# Buttoninterface.net
KiCad netlist of a schematic drawn in Altium Designer
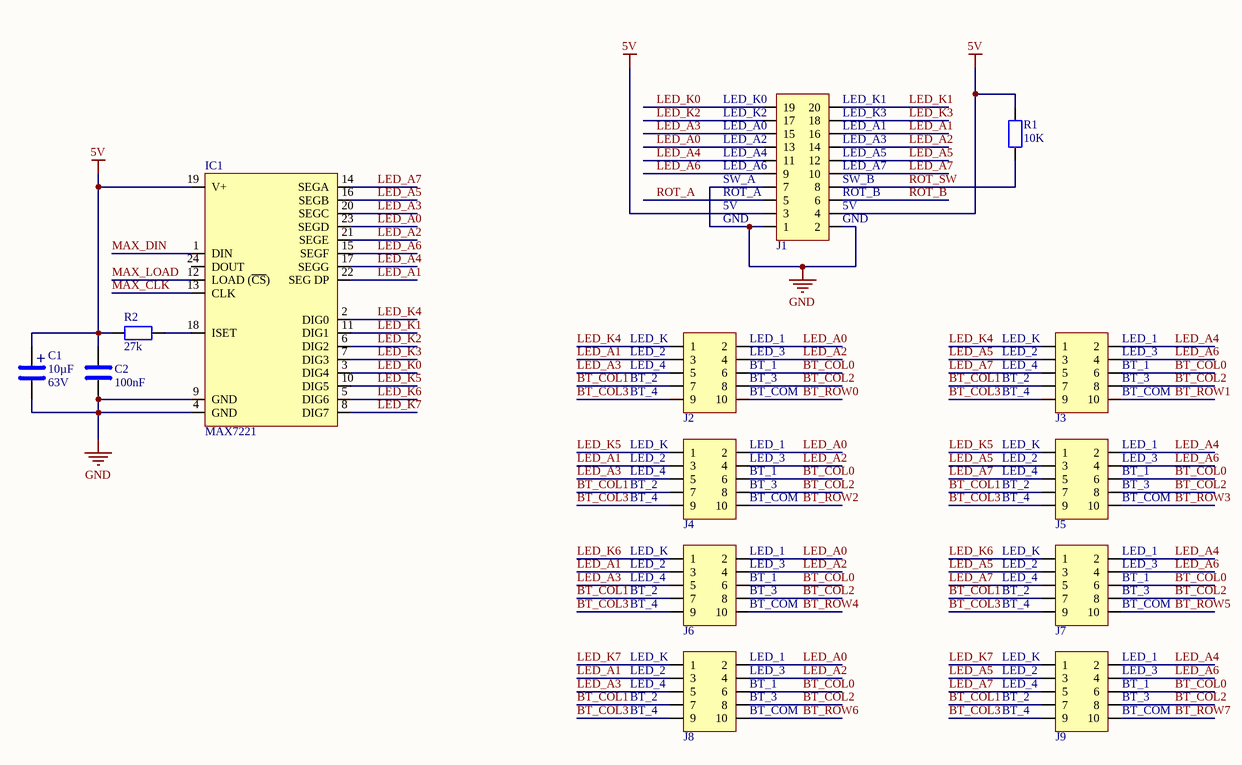
[diagram p0: Buttoninterface.SchDoc]

(export (version "E")
  (design (tool "Eeschema 10.0.6"))
  (components
    (comp (ref "C1")
      (value "10µF")
      (footprint "RM2D5H11")
      (fields (field (name "VOLTAGE") "63V") (field (name "Comment") "Elko_10uF_63V"))
      (libsource (lib "elkos") (part "Elko_10uF_63V"))
    )
    (comp (ref "C2")
      (value "100nF")
      (footprint "0805")
      (description "100nF 50V MLCC 0805")
      (fields (field (name "VOLTAGE") "50V"))
      (libsource (lib "capacitors") (part "100nF 50V MLCC 0805"))
    )
    (comp (ref "IC1")
      (value "MAX7221")
      (footprint "DIL28")
      (description "8x8 Matrix LED driver")
      (libsource (lib "misc") (part "MAX7221CNG"))
    )
    (comp (ref "J1")
      (value "Wannenstecker 20pol 2,54mm")
      (footprint "WSL20G")
      (libsource (lib "wannenstecker") (part "Wannenstecker 20pol 2,54mm"))
    )
    (comp (ref "J2")
      (value "Wannenstecker 10pol 2,54mm")
      (footprint "WSL10G")
      (libsource (lib "wannenstecker") (part "Wannenstecker 10pol 2,54mm"))
    )
    (comp (ref "J3")
      (value "Wannenstecker 10pol 2,54mm")
      (footprint "WSL10G")
      (libsource (lib "wannenstecker") (part "Wannenstecker 10pol 2,54mm"))
    )
    (comp (ref "J4")
      (value "Wannenstecker 10pol 2,54mm")
      (footprint "WSL10G")
      (libsource (lib "wannenstecker") (part "Wannenstecker 10pol 2,54mm"))
    )
    (comp (ref "J5")
      (value "Wannenstecker 10pol 2,54mm")
      (footprint "WSL10G")
      (libsource (lib "wannenstecker") (part "Wannenstecker 10pol 2,54mm"))
    )
    (comp (ref "J6")
      (value "Wannenstecker 10pol 2,54mm")
      (footprint "WSL10G")
      (libsource (lib "wannenstecker") (part "Wannenstecker 10pol 2,54mm"))
    )
    (comp (ref "J7")
      (value "Wannenstecker 10pol 2,54mm")
      (footprint "WSL10G")
      (libsource (lib "wannenstecker") (part "Wannenstecker 10pol 2,54mm"))
    )
    (comp (ref "J8")
      (value "Wannenstecker 10pol 2,54mm")
      (footprint "WSL10G")
      (libsource (lib "wannenstecker") (part "Wannenstecker 10pol 2,54mm"))
    )
    (comp (ref "J9")
      (value "Wannenstecker 10pol 2,54mm")
      (footprint "WSL10G")
      (libsource (lib "wannenstecker") (part "Wannenstecker 10pol 2,54mm"))
    )
    (comp (ref "R1")
      (value "10K")
      (footprint "res0805")
      (description "10K 125mW 0805")
      (fields (field (name "TOLERANCE") "1%"))
      (libsource (lib "resistors") (part "10K 125mW 0805"))
    )
    (comp (ref "R2")
      (value "27k")
      (footprint "res0805")
      (description "27k 125mW 0805")
      (fields (field (name "TOLERANCE") "1%"))
      (libsource (lib "resistors") (part "27k 125mW 0805"))
    )
  )
  (nets
    (net (code "1") (name "/BT_COL0") (class "Default")
      (node (ref "J2") (pin "6") (pinfunction "6_6") (pintype "passive"))
      (node (ref "J3") (pin "6") (pinfunction "6_6") (pintype "passive"))
      (node (ref "J4") (pin "6") (pinfunction "6_6") (pintype "passive"))
      (node (ref "J5") (pin "6") (pinfunction "6_6") (pintype "passive"))
      (node (ref "J6") (pin "6") (pinfunction "6_6") (pintype "passive"))
      (node (ref "J7") (pin "6") (pinfunction "6_6") (pintype "passive"))
      (node (ref "J8") (pin "6") (pinfunction "6_6") (pintype "passive"))
      (node (ref "J9") (pin "6") (pinfunction "6_6") (pintype "passive"))
    )
    (net (code "2") (name "/BT_COL1") (class "Default")
      (node (ref "J2") (pin "7") (pinfunction "7_7") (pintype "passive"))
      (node (ref "J3") (pin "7") (pinfunction "7_7") (pintype "passive"))
      (node (ref "J4") (pin "7") (pinfunction "7_7") (pintype "passive"))
      (node (ref "J5") (pin "7") (pinfunction "7_7") (pintype "passive"))
      (node (ref "J6") (pin "7") (pinfunction "7_7") (pintype "passive"))
      (node (ref "J7") (pin "7") (pinfunction "7_7") (pintype "passive"))
      (node (ref "J8") (pin "7") (pinfunction "7_7") (pintype "passive"))
      (node (ref "J9") (pin "7") (pinfunction "7_7") (pintype "passive"))
    )
    (net (code "3") (name "/BT_COL2") (class "Default")
      (node (ref "J2") (pin "8") (pinfunction "8_8") (pintype "passive"))
      (node (ref "J3") (pin "8") (pinfunction "8_8") (pintype "passive"))
      (node (ref "J4") (pin "8") (pinfunction "8_8") (pintype "passive"))
      (node (ref "J5") (pin "8") (pinfunction "8_8") (pintype "passive"))
      (node (ref "J6") (pin "8") (pinfunction "8_8") (pintype "passive"))
      (node (ref "J7") (pin "8") (pinfunction "8_8") (pintype "passive"))
      (node (ref "J8") (pin "8") (pinfunction "8_8") (pintype "passive"))
      (node (ref "J9") (pin "8") (pinfunction "8_8") (pintype "passive"))
    )
    (net (code "4") (name "/BT_COL3") (class "Default")
      (node (ref "J2") (pin "9") (pinfunction "9_9") (pintype "passive"))
      (node (ref "J3") (pin "9") (pinfunction "9_9") (pintype "passive"))
      (node (ref "J4") (pin "9") (pinfunction "9_9") (pintype "passive"))
      (node (ref "J5") (pin "9") (pinfunction "9_9") (pintype "passive"))
      (node (ref "J6") (pin "9") (pinfunction "9_9") (pintype "passive"))
      (node (ref "J7") (pin "9") (pinfunction "9_9") (pintype "passive"))
      (node (ref "J8") (pin "9") (pinfunction "9_9") (pintype "passive"))
      (node (ref "J9") (pin "9") (pinfunction "9_9") (pintype "passive"))
    )
    (net (code "5") (name "/BT_ROW0") (class "Default")
      (node (ref "J2") (pin "10") (pinfunction "10_10") (pintype "passive"))
    )
    (net (code "6") (name "/BT_ROW1") (class "Default")
      (node (ref "J3") (pin "10") (pinfunction "10_10") (pintype "passive"))
    )
    (net (code "7") (name "/BT_ROW2") (class "Default")
      (node (ref "J4") (pin "10") (pinfunction "10_10") (pintype "passive"))
    )
    (net (code "8") (name "/BT_ROW3") (class "Default")
      (node (ref "J5") (pin "10") (pinfunction "10_10") (pintype "passive"))
    )
    (net (code "9") (name "/BT_ROW4") (class "Default")
      (node (ref "J6") (pin "10") (pinfunction "10_10") (pintype "passive"))
    )
    (net (code "10") (name "/BT_ROW5") (class "Default")
      (node (ref "J7") (pin "10") (pinfunction "10_10") (pintype "passive"))
    )
    (net (code "11") (name "/BT_ROW6") (class "Default")
      (node (ref "J8") (pin "10") (pinfunction "10_10") (pintype "passive"))
    )
    (net (code "12") (name "/BT_ROW7") (class "Default")
      (node (ref "J9") (pin "10") (pinfunction "10_10") (pintype "passive"))
    )
    (net (code "13") (name "/LED_A0") (class "Default")
      (node (ref "IC1") (pin "23") (pinfunction "SEGD_23") (pintype "passive"))
      (node (ref "J1") (pin "13") (pinfunction "13_13") (pintype "passive"))
      (node (ref "J2") (pin "2") (pinfunction "2_2") (pintype "passive"))
      (node (ref "J4") (pin "2") (pinfunction "2_2") (pintype "passive"))
      (node (ref "J6") (pin "2") (pinfunction "2_2") (pintype "passive"))
      (node (ref "J8") (pin "2") (pinfunction "2_2") (pintype "passive"))
    )
    (net (code "14") (name "/LED_A1") (class "Default")
      (node (ref "IC1") (pin "22") (pinfunction "SEG_DP_22") (pintype "passive"))
      (node (ref "J1") (pin "16") (pinfunction "16_16") (pintype "passive"))
      (node (ref "J2") (pin "3") (pinfunction "3_3") (pintype "passive"))
      (node (ref "J4") (pin "3") (pinfunction "3_3") (pintype "passive"))
      (node (ref "J6") (pin "3") (pinfunction "3_3") (pintype "passive"))
      (node (ref "J8") (pin "3") (pinfunction "3_3") (pintype "passive"))
    )
    (net (code "15") (name "/LED_A2") (class "Default")
      (node (ref "IC1") (pin "21") (pinfunction "SEGE_21") (pintype "passive"))
      (node (ref "J1") (pin "14") (pinfunction "14_14") (pintype "passive"))
      (node (ref "J2") (pin "4") (pinfunction "4_4") (pintype "passive"))
      (node (ref "J4") (pin "4") (pinfunction "4_4") (pintype "passive"))
      (node (ref "J6") (pin "4") (pinfunction "4_4") (pintype "passive"))
      (node (ref "J8") (pin "4") (pinfunction "4_4") (pintype "passive"))
    )
    (net (code "16") (name "/LED_A3") (class "Default")
      (node (ref "IC1") (pin "20") (pinfunction "SEGC_20") (pintype "passive"))
      (node (ref "J1") (pin "15") (pinfunction "15_15") (pintype "passive"))
      (node (ref "J2") (pin "5") (pinfunction "5_5") (pintype "passive"))
      (node (ref "J4") (pin "5") (pinfunction "5_5") (pintype "passive"))
      (node (ref "J6") (pin "5") (pinfunction "5_5") (pintype "passive"))
      (node (ref "J8") (pin "5") (pinfunction "5_5") (pintype "passive"))
    )
    (net (code "17") (name "/LED_A4") (class "Default")
      (node (ref "IC1") (pin "17") (pinfunction "SEGG_17") (pintype "passive"))
      (node (ref "J1") (pin "11") (pinfunction "11_11") (pintype "passive"))
      (node (ref "J3") (pin "2") (pinfunction "2_2") (pintype "passive"))
      (node (ref "J5") (pin "2") (pinfunction "2_2") (pintype "passive"))
      (node (ref "J7") (pin "2") (pinfunction "2_2") (pintype "passive"))
      (node (ref "J9") (pin "2") (pinfunction "2_2") (pintype "passive"))
    )
    (net (code "18") (name "/LED_A5") (class "Default")
      (node (ref "IC1") (pin "16") (pinfunction "SEGB_16") (pintype "passive"))
      (node (ref "J1") (pin "12") (pinfunction "12_12") (pintype "passive"))
      (node (ref "J3") (pin "3") (pinfunction "3_3") (pintype "passive"))
      (node (ref "J5") (pin "3") (pinfunction "3_3") (pintype "passive"))
      (node (ref "J7") (pin "3") (pinfunction "3_3") (pintype "passive"))
      (node (ref "J9") (pin "3") (pinfunction "3_3") (pintype "passive"))
    )
    (net (code "19") (name "/LED_A6") (class "Default")
      (node (ref "IC1") (pin "15") (pinfunction "SEGF_15") (pintype "passive"))
      (node (ref "J1") (pin "9") (pinfunction "9_9") (pintype "passive"))
      (node (ref "J3") (pin "4") (pinfunction "4_4") (pintype "passive"))
      (node (ref "J5") (pin "4") (pinfunction "4_4") (pintype "passive"))
      (node (ref "J7") (pin "4") (pinfunction "4_4") (pintype "passive"))
      (node (ref "J9") (pin "4") (pinfunction "4_4") (pintype "passive"))
    )
    (net (code "20") (name "/LED_A7") (class "Default")
      (node (ref "IC1") (pin "14") (pinfunction "SEGA_14") (pintype "passive"))
      (node (ref "J1") (pin "10") (pinfunction "10_10") (pintype "passive"))
      (node (ref "J3") (pin "5") (pinfunction "5_5") (pintype "passive"))
      (node (ref "J5") (pin "5") (pinfunction "5_5") (pintype "passive"))
      (node (ref "J7") (pin "5") (pinfunction "5_5") (pintype "passive"))
      (node (ref "J9") (pin "5") (pinfunction "5_5") (pintype "passive"))
    )
    (net (code "21") (name "/LED_K0") (class "Default")
      (node (ref "IC1") (pin "3") (pinfunction "DIG4_3") (pintype "passive"))
      (node (ref "J1") (pin "19") (pinfunction "19_19") (pintype "passive"))
    )
    (net (code "22") (name "/LED_K1") (class "Default")
      (node (ref "IC1") (pin "11") (pinfunction "DIG1_11") (pintype "passive"))
      (node (ref "J1") (pin "20") (pinfunction "20_20") (pintype "passive"))
    )
    (net (code "23") (name "/LED_K2") (class "Default")
      (node (ref "IC1") (pin "6") (pinfunction "DIG2_6") (pintype "passive"))
      (node (ref "J1") (pin "17") (pinfunction "17_17") (pintype "passive"))
    )
    (net (code "24") (name "/LED_K3") (class "Default")
      (node (ref "IC1") (pin "7") (pinfunction "DIG3_7") (pintype "passive"))
      (node (ref "J1") (pin "18") (pinfunction "18_18") (pintype "passive"))
    )
    (net (code "25") (name "/LED_K4") (class "Default")
      (node (ref "IC1") (pin "2") (pinfunction "DIG0_2") (pintype "passive"))
      (node (ref "J2") (pin "1") (pinfunction "1_1") (pintype "passive"))
      (node (ref "J3") (pin "1") (pinfunction "1_1") (pintype "passive"))
    )
    (net (code "26") (name "/LED_K5") (class "Default")
      (node (ref "IC1") (pin "10") (pinfunction "DIG5_10") (pintype "passive"))
      (node (ref "J4") (pin "1") (pinfunction "1_1") (pintype "passive"))
      (node (ref "J5") (pin "1") (pinfunction "1_1") (pintype "passive"))
    )
    (net (code "27") (name "/LED_K6") (class "Default")
      (node (ref "IC1") (pin "5") (pinfunction "DIG6_5") (pintype "passive"))
      (node (ref "J6") (pin "1") (pinfunction "1_1") (pintype "passive"))
      (node (ref "J7") (pin "1") (pinfunction "1_1") (pintype "passive"))
    )
    (net (code "28") (name "/LED_K7") (class "Default")
      (node (ref "IC1") (pin "8") (pinfunction "DIG7_8") (pintype "passive"))
      (node (ref "J8") (pin "1") (pinfunction "1_1") (pintype "passive"))
      (node (ref "J9") (pin "1") (pinfunction "1_1") (pintype "passive"))
    )
    (net (code "29") (name "/MAX_CLK") (class "Default")
      (node (ref "IC1") (pin "13") (pinfunction "CLK_13") (pintype "passive"))
    )
    (net (code "30") (name "/MAX_DIN") (class "Default")
      (node (ref "IC1") (pin "1") (pinfunction "DIN_1") (pintype "passive"))
    )
    (net (code "31") (name "/MAX_LOAD") (class "Default")
      (node (ref "IC1") (pin "12") (pinfunction "LOAD_(~{CS})_12") (pintype "passive"))
    )
    (net (code "32") (name "/ROT_A") (class "Default")
      (node (ref "J1") (pin "5") (pinfunction "5_5") (pintype "passive"))
    )
    (net (code "33") (name "/ROT_B") (class "Default")
      (node (ref "J1") (pin "6") (pinfunction "6_6") (pintype "passive"))
    )
    (net (code "34") (name "/ROT_SW") (class "Default")
      (node (ref "J1") (pin "8") (pinfunction "8_8") (pintype "passive"))
      (node (ref "R1") (pin "1") (pinfunction "1_1") (pintype "passive"))
    )
    (net (code "35") (name "5V") (class "Default")
      (node (ref "C1") (pin "+") (pinfunction "+_+") (pintype "passive"))
      (node (ref "C2") (pin "2") (pinfunction "2_2") (pintype "passive"))
      (node (ref "IC1") (pin "19") (pinfunction "V+_19") (pintype "passive"))
      (node (ref "J1") (pin "3") (pinfunction "3_3") (pintype "passive"))
      (node (ref "J1") (pin "4") (pinfunction "4_4") (pintype "passive"))
      (node (ref "R1") (pin "2") (pinfunction "2_2") (pintype "passive"))
      (node (ref "R2") (pin "2") (pinfunction "2_2") (pintype "passive"))
    )
    (net (code "36") (name "GND") (class "Default")
      (node (ref "C1") (pin "-") (pinfunction "-_-") (pintype "passive"))
      (node (ref "C2") (pin "1") (pinfunction "1_1") (pintype "passive"))
      (node (ref "IC1") (pin "4") (pinfunction "GND_4") (pintype "passive"))
      (node (ref "IC1") (pin "9") (pinfunction "GND_9") (pintype "passive"))
      (node (ref "J1") (pin "1") (pinfunction "1_1") (pintype "passive"))
      (node (ref "J1") (pin "2") (pinfunction "2_2") (pintype "passive"))
      (node (ref "J1") (pin "7") (pinfunction "7_7") (pintype "passive"))
    )
    (net (code "37") (name "Net-(IC1-ISET)") (class "Default")
      (node (ref "IC1") (pin "18") (pinfunction "ISET_18") (pintype "passive"))
      (node (ref "R2") (pin "1") (pinfunction "1_1") (pintype "passive"))
    )
    (net (code "38") (name "unconnected-(IC1-DOUT-Pad24)") (class "Default")
      (node (ref "IC1") (pin "24") (pinfunction "DOUT_24") (pintype "passive"))
    )
  )
)
